# E73N30.net
KiCad netlist of a schematic drawn in Altium Designer
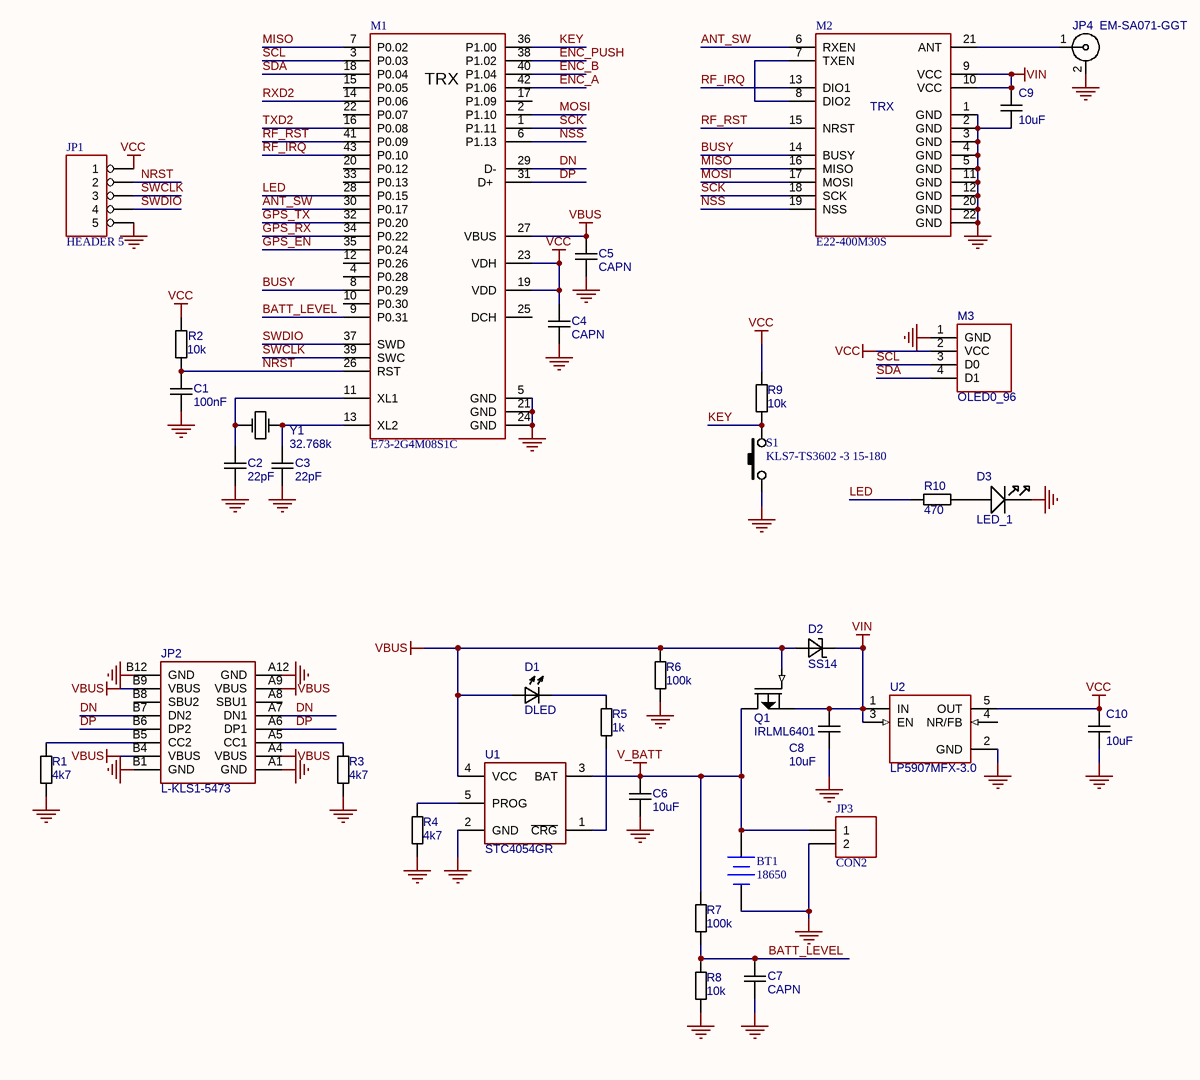
[diagram p0: E73N30.SchDoc]

(export (version "E")
  (design (tool "Eeschema 10.0.6"))
  (components
    (comp (ref "BT1")
      (value "18650")
      (footprint "18650")
      (description "Multicell Battery")
      (fields (field (name "PUBLISHER") "Altium Limited"))
      (libsource (lib "zucker") (part "Battery"))
    )
    (comp (ref "C1")
      (value "100nF")
      (footprint "C-0603")
      (fields (field (name "VOLTAGE") "50V"))
      (libsource (lib "Passive") (part "CAPN"))
    )
    (comp (ref "C2")
      (value "22pF")
      (footprint "C-0603")
      (fields (field (name "VOLTAGE") "50V"))
      (libsource (lib "Passive") (part "CAPN"))
    )
    (comp (ref "C3")
      (value "22pF")
      (footprint "C-0603")
      (fields (field (name "VOLTAGE") "50V"))
      (libsource (lib "Passive") (part "CAPN"))
    )
    (comp (ref "C4")
      (value "CAPN")
      (footprint "C-0603")
      (fields (field (name "VOLTAGE") "50V"))
      (libsource (lib "Passive") (part "CAPN"))
    )
    (comp (ref "C5")
      (value "CAPN")
      (footprint "C-0603")
      (fields (field (name "VOLTAGE") "50V"))
      (libsource (lib "Passive") (part "CAPN"))
    )
    (comp (ref "C6")
      (value "10uF")
      (footprint "C-0805")
      (fields (field (name "VOLTAGE") "50V"))
      (libsource (lib "Passive") (part "CAPN"))
    )
    (comp (ref "C7")
      (value "CAPN")
      (footprint "C-0603")
      (fields (field (name "VOLTAGE") "50V"))
      (libsource (lib "Passive") (part "CAPN"))
    )
    (comp (ref "C8")
      (value "10uF")
      (footprint "C-0805")
      (fields (field (name "VOLTAGE") "50V"))
      (libsource (lib "Passive") (part "CAPN"))
    )
    (comp (ref "C9")
      (value "10uF")
      (footprint "C-0805")
      (fields (field (name "VOLTAGE") "50V"))
      (libsource (lib "Passive") (part "CAPN"))
    )
    (comp (ref "C10")
      (value "10uF")
      (footprint "C-0805")
      (fields (field (name "VOLTAGE") "50V"))
      (libsource (lib "Passive") (part "CAPN"))
    )
    (comp (ref "D1") (value "DLED") (footprint "LED0805") (libsource (lib "Diodes") (part "DLED")))
    (comp (ref "D2") (value "SS14") (footprint "D-SMA") (libsource (lib "Diodes") (part "DIODSH")))
    (comp (ref "D3") (value "LED_1") (footprint "LED_0805") (libsource (lib "Diodes") (part "LED_1")))
    (comp (ref "JP1")
      (value "HEADER 5")
      (footprint "PLS1-5")
      (libsource (lib "Connectors") (part "HEADER 5"))
    )
    (comp (ref "JP2")
      (value "L-KLS1-5473")
      (footprint "USB_C_SMD_SLOT")
      (libsource (lib "Connectors") (part "L-KLS1-5473"))
    )
    (comp (ref "JP3") (value "CON2") (footprint "WH-02R") (libsource (lib "Connectors") (part "CON2")))
    (comp (ref "JP4")
      (value "EM-SA071-GGT")
      (footprint "SMA_F_EDGE")
      (description "SMA Female R/A PCB Mount")
      (libsource (lib "Connectors") (part "SMA"))
    )
    (comp (ref "M1")
      (value "E73-2G4M08S1C")
      (footprint "E73-2G4M08S1CX")
      (libsource (lib "RFmodules") (part "E73-2G4M08S1C"))
    )
    (comp (ref "M2")
      (value "E22-400M30S")
      (footprint "PE22(400M30S)")
      (libsource (lib "RFmodules") (part "E22"))
    )
    (comp (ref "M3")
      (value "OLED0_96")
      (footprint "OLED096_I2C")
      (libsource (lib "RFmodules") (part "OLED0_96_I2C"))
    )
    (comp (ref "Q1") (value "IRLML6401") (footprint "SOT-23") (libsource (lib "Discrete") (part "MOSF-P")))
    (comp (ref "R1") (value "4k7") (footprint "R-0603") (libsource (lib "") (part "RES_1")))
    (comp (ref "R2") (value "10k") (footprint "R-0603") (libsource (lib "Passive") (part "RES")))
    (comp (ref "R3") (value "4k7") (footprint "R-0603") (libsource (lib "") (part "RES_1")))
    (comp (ref "R4") (value "4k7") (footprint "R-0603") (libsource (lib "") (part "RES_1")))
    (comp (ref "R5") (value "1k") (footprint "R-0603") (libsource (lib "Passive") (part "RES")))
    (comp (ref "R6") (value "100k") (footprint "R-0603") (libsource (lib "Passive") (part "RES")))
    (comp (ref "R7") (value "100k") (footprint "R-0603") (libsource (lib "Passive") (part "RES")))
    (comp (ref "R8") (value "10k") (footprint "R-0603") (libsource (lib "Passive") (part "RES")))
    (comp (ref "R9") (value "10k") (footprint "R-0603") (libsource (lib "") (part "RES_3")))
    (comp (ref "R10") (value "470") (footprint "R-0603") (libsource (lib "") (part "RES_2")))
    (comp (ref "S1")
      (value "KLS7-TS3602 -3 15-180")
      (footprint "KN_MIN")
      (libsource (lib "Switches") (part "SW-1"))
    )
    (comp (ref "U1") (value "STC4054GR") (footprint "SOT-23-5") (libsource (lib "Power") (part "STC4054")))
    (comp (ref "U2")
      (value "LP5907MFX-3.0")
      (footprint "SOT-23-5")
      (description "250mA Low-Dropout Regulator")
      (libsource (lib "ICs") (part "LP5907"))
    )
    (comp (ref "Y1") (value "32.768k") (footprint "KX-327") (libsource (lib "Passive") (part "Y")))
  )
  (nets
    (net (code "1") (name "/ANT_SW") (class "Default")
      (node (ref "M1") (pin "30") (pinfunction "P0.17_30") (pintype "passive"))
      (node (ref "M2") (pin "6") (pinfunction "RXEN_6") (pintype "passive"))
    )
    (net (code "2") (name "/BATT_LEVEL") (class "Default")
      (node (ref "C7") (pin "1") (pinfunction "1_1") (pintype "passive"))
      (node (ref "M1") (pin "9") (pinfunction "P0.31_9") (pintype "passive"))
      (node (ref "R7") (pin "1") (pinfunction "1_1") (pintype "passive"))
      (node (ref "R8") (pin "2") (pinfunction "2_2") (pintype "passive"))
    )
    (net (code "3") (name "/BUSY") (class "Default")
      (node (ref "M1") (pin "8") (pinfunction "P0.29_8") (pintype "passive"))
      (node (ref "M2") (pin "14") (pinfunction "BUSY_14") (pintype "passive"))
    )
    (net (code "4") (name "/DN") (class "Default")
      (node (ref "JP2") (pin "A7") (pinfunction "DN1_A7") (pintype "passive"))
      (node (ref "JP2") (pin "B7") (pinfunction "DN2_B7") (pintype "passive"))
      (node (ref "M1") (pin "29") (pinfunction "D-_29") (pintype "passive"))
    )
    (net (code "5") (name "/DP") (class "Default")
      (node (ref "JP2") (pin "A6") (pinfunction "DP1_A6") (pintype "passive"))
      (node (ref "JP2") (pin "B6") (pinfunction "DP2_B6") (pintype "passive"))
      (node (ref "M1") (pin "31") (pinfunction "D+_31") (pintype "passive"))
    )
    (net (code "6") (name "/ENC_A") (class "Default")
      (node (ref "M1") (pin "42") (pinfunction "P1.06_42") (pintype "passive"))
    )
    (net (code "7") (name "/ENC_B") (class "Default")
      (node (ref "M1") (pin "40") (pinfunction "P1.04_40") (pintype "passive"))
    )
    (net (code "8") (name "/ENC_PUSH") (class "Default")
      (node (ref "M1") (pin "38") (pinfunction "P1.02_38") (pintype "passive"))
    )
    (net (code "9") (name "/GPS_EN") (class "Default")
      (node (ref "M1") (pin "35") (pinfunction "P0.24_35") (pintype "passive"))
    )
    (net (code "10") (name "/GPS_RX") (class "Default")
      (node (ref "M1") (pin "34") (pinfunction "P0.22_34") (pintype "passive"))
    )
    (net (code "11") (name "/GPS_TX") (class "Default")
      (node (ref "M1") (pin "32") (pinfunction "P0.20_32") (pintype "passive"))
    )
    (net (code "12") (name "/KEY") (class "Default")
      (node (ref "M1") (pin "36") (pinfunction "P1.00_36") (pintype "passive"))
      (node (ref "R9") (pin "2") (pinfunction "2_2") (pintype "passive"))
      (node (ref "S1") (pin "2") (pinfunction "2_2") (pintype "passive"))
    )
    (net (code "13") (name "/LED") (class "Default")
      (node (ref "M1") (pin "28") (pinfunction "P0.15_28") (pintype "passive"))
      (node (ref "R10") (pin "2") (pinfunction "2_2") (pintype "passive"))
    )
    (net (code "14") (name "/MISO") (class "Default")
      (node (ref "M1") (pin "7") (pinfunction "P0.02_7") (pintype "passive"))
      (node (ref "M2") (pin "16") (pinfunction "MISO_16") (pintype "passive"))
    )
    (net (code "15") (name "/MOSI") (class "Default")
      (node (ref "M1") (pin "2") (pinfunction "P1.10_2") (pintype "passive"))
      (node (ref "M2") (pin "17") (pinfunction "MOSI_17") (pintype "passive"))
    )
    (net (code "16") (name "/NRST") (class "Default")
      (node (ref "C1") (pin "2") (pinfunction "2_2") (pintype "passive"))
      (node (ref "JP1") (pin "2") (pinfunction "2_2") (pintype "passive"))
      (node (ref "M1") (pin "26") (pinfunction "RST_26") (pintype "passive"))
      (node (ref "R2") (pin "1") (pinfunction "1_1") (pintype "passive"))
    )
    (net (code "17") (name "/NSS") (class "Default")
      (node (ref "M1") (pin "6") (pinfunction "P1.13_6") (pintype "passive"))
      (node (ref "M2") (pin "19") (pinfunction "NSS_19") (pintype "passive"))
    )
    (net (code "18") (name "/RF_IRQ") (class "Default")
      (node (ref "M1") (pin "43") (pinfunction "P0.10_43") (pintype "passive"))
      (node (ref "M2") (pin "13") (pinfunction "DIO1_13") (pintype "passive"))
    )
    (net (code "19") (name "/RF_RST") (class "Default")
      (node (ref "M1") (pin "41") (pinfunction "P0.09_41") (pintype "passive"))
      (node (ref "M2") (pin "15") (pinfunction "NRST_15") (pintype "passive"))
    )
    (net (code "20") (name "/RXD2") (class "Default")
      (node (ref "M1") (pin "14") (pinfunction "P0.06_14") (pintype "passive"))
    )
    (net (code "21") (name "/SCK") (class "Default")
      (node (ref "M1") (pin "1") (pinfunction "_P1.11_1") (pintype "passive"))
      (node (ref "M2") (pin "18") (pinfunction "SCK_18") (pintype "passive"))
    )
    (net (code "22") (name "/SCL") (class "Default")
      (node (ref "M1") (pin "3") (pinfunction "P0.03_3") (pintype "passive"))
      (node (ref "M3") (pin "3") (pinfunction "D0_3") (pintype "passive"))
    )
    (net (code "23") (name "/SDA") (class "Default")
      (node (ref "M1") (pin "18") (pinfunction "P0.04_18") (pintype "passive"))
      (node (ref "M3") (pin "4") (pinfunction "D1_4") (pintype "passive"))
    )
    (net (code "24") (name "/SWCLK") (class "Default")
      (node (ref "JP1") (pin "3") (pinfunction "3_3") (pintype "passive"))
      (node (ref "M1") (pin "39") (pinfunction "SWC_39") (pintype "passive"))
    )
    (net (code "25") (name "/SWDIO") (class "Default")
      (node (ref "JP1") (pin "4") (pinfunction "4_4") (pintype "passive"))
      (node (ref "M1") (pin "37") (pinfunction "SWD_37") (pintype "passive"))
    )
    (net (code "26") (name "/TXD2") (class "Default")
      (node (ref "M1") (pin "16") (pinfunction "P0.08_16") (pintype "passive"))
    )
    (net (code "27") (name "GND") (class "Default")
      (node (ref "BT1") (pin "2") (pinfunction "-_2") (pintype "passive"))
      (node (ref "C1") (pin "1") (pinfunction "1_1") (pintype "passive"))
      (node (ref "C10") (pin "2") (pinfunction "2_2") (pintype "passive"))
      (node (ref "C2") (pin "1") (pinfunction "1_1") (pintype "passive"))
      (node (ref "C3") (pin "1") (pinfunction "1_1") (pintype "passive"))
      (node (ref "C4") (pin "2") (pinfunction "2_2") (pintype "passive"))
      (node (ref "C5") (pin "2") (pinfunction "2_2") (pintype "passive"))
      (node (ref "C6") (pin "2") (pinfunction "2_2") (pintype "passive"))
      (node (ref "C7") (pin "2") (pinfunction "2_2") (pintype "passive"))
      (node (ref "C8") (pin "2") (pinfunction "2_2") (pintype "passive"))
      (node (ref "C9") (pin "2") (pinfunction "2_2") (pintype "passive"))
      (node (ref "D3") (pin "K") (pinfunction "CATHODE_K") (pintype "passive"))
      (node (ref "JP1") (pin "5") (pinfunction "5_5") (pintype "passive"))
      (node (ref "JP2") (pin "A1") (pinfunction "GND_A1") (pintype "passive"))
      (node (ref "JP2") (pin "A12") (pinfunction "GND_A12") (pintype "passive"))
      (node (ref "JP2") (pin "B1") (pinfunction "GND_B1") (pintype "passive"))
      (node (ref "JP2") (pin "B12") (pinfunction "GND_B12") (pintype "passive"))
      (node (ref "JP3") (pin "2") (pinfunction "2_2") (pintype "passive"))
      (node (ref "JP4") (pin "2") (pinfunction "2_2") (pintype "passive"))
      (node (ref "M1") (pin "21") (pinfunction "GND_21") (pintype "passive"))
      (node (ref "M1") (pin "24") (pinfunction "GND_24") (pintype "passive"))
      (node (ref "M1") (pin "5") (pinfunction "GND_5") (pintype "passive"))
      (node (ref "M2") (pin "1") (pinfunction "GND_1") (pintype "passive"))
      (node (ref "M2") (pin "11") (pinfunction "GND_11") (pintype "passive"))
      (node (ref "M2") (pin "12") (pinfunction "GND_12") (pintype "passive"))
      (node (ref "M2") (pin "2") (pinfunction "GND_2") (pintype "passive"))
      (node (ref "M2") (pin "20") (pinfunction "GND_20") (pintype "passive"))
      (node (ref "M2") (pin "22") (pinfunction "GND_22") (pintype "passive"))
      (node (ref "M2") (pin "3") (pinfunction "GND_3") (pintype "passive"))
      (node (ref "M2") (pin "4") (pinfunction "GND_4") (pintype "passive"))
      (node (ref "M2") (pin "5") (pinfunction "GND_5") (pintype "passive"))
      (node (ref "M3") (pin "1") (pinfunction "GND_1") (pintype "passive"))
      (node (ref "R1") (pin "1") (pinfunction "1_1") (pintype "passive"))
      (node (ref "R3") (pin "1") (pinfunction "1_1") (pintype "passive"))
      (node (ref "R4") (pin "1") (pinfunction "1_1") (pintype "passive"))
      (node (ref "R6") (pin "1") (pinfunction "1_1") (pintype "passive"))
      (node (ref "R8") (pin "1") (pinfunction "1_1") (pintype "passive"))
      (node (ref "S1") (pin "1") (pinfunction "1_1") (pintype "passive"))
      (node (ref "U1") (pin "2") (pinfunction "GND_2") (pintype "passive"))
      (node (ref "U2") (pin "2") (pinfunction "GND_2") (pintype "power_in"))
    )
    (net (code "28") (name "Net-(D1-Pad2)") (class "Default")
      (node (ref "D1") (pin "2") (pinfunction "2_2") (pintype "passive"))
      (node (ref "R5") (pin "2") (pinfunction "2_2") (pintype "passive"))
    )
    (net (code "29") (name "Net-(D3-ANODE)") (class "Default")
      (node (ref "D3") (pin "A") (pinfunction "ANODE_A") (pintype "passive"))
      (node (ref "R10") (pin "1") (pinfunction "1_1") (pintype "passive"))
    )
    (net (code "30") (name "Net-(JP2-CC1)") (class "Default")
      (node (ref "JP2") (pin "A5") (pinfunction "CC1_A5") (pintype "passive"))
      (node (ref "R3") (pin "2") (pinfunction "2_2") (pintype "passive"))
    )
    (net (code "31") (name "Net-(JP2-CC2)") (class "Default")
      (node (ref "JP2") (pin "B5") (pinfunction "CC2_B5") (pintype "passive"))
      (node (ref "R1") (pin "2") (pinfunction "2_2") (pintype "passive"))
    )
    (net (code "32") (name "Net-(M1-XL1)") (class "Default")
      (node (ref "C2") (pin "2") (pinfunction "2_2") (pintype "passive"))
      (node (ref "M1") (pin "11") (pinfunction "XL1_11") (pintype "passive"))
      (node (ref "Y1") (pin "2") (pinfunction "2_2") (pintype "passive"))
    )
    (net (code "33") (name "Net-(M1-XL2)") (class "Default")
      (node (ref "C3") (pin "2") (pinfunction "2_2") (pintype "passive"))
      (node (ref "M1") (pin "13") (pinfunction "XL2_13") (pintype "passive"))
      (node (ref "Y1") (pin "1") (pinfunction "1_1") (pintype "passive"))
    )
    (net (code "34") (name "Net-(M2-ANT)") (class "Default")
      (node (ref "JP4") (pin "1") (pinfunction "1_1") (pintype "passive"))
      (node (ref "M2") (pin "21") (pinfunction "ANT_21") (pintype "passive"))
    )
    (net (code "35") (name "Net-(M2-DIO2)") (class "Default")
      (node (ref "M2") (pin "7") (pinfunction "TXEN_7") (pintype "passive"))
      (node (ref "M2") (pin "8") (pinfunction "DIO2_8") (pintype "passive"))
    )
    (net (code "36") (name "Net-(U1-PROG)") (class "Default")
      (node (ref "R4") (pin "2") (pinfunction "2_2") (pintype "passive"))
      (node (ref "U1") (pin "5") (pinfunction "PROG_5") (pintype "passive"))
    )
    (net (code "37") (name "Net-(U1-~{CRG})") (class "Default")
      (node (ref "R5") (pin "1") (pinfunction "1_1") (pintype "passive"))
      (node (ref "U1") (pin "1") (pinfunction "~{CRG}_1") (pintype "passive"))
    )
    (net (code "38") (name "VBUS") (class "Default")
      (node (ref "C5") (pin "1") (pinfunction "1_1") (pintype "passive"))
      (node (ref "D1") (pin "1") (pinfunction "1_1") (pintype "passive"))
      (node (ref "D2") (pin "1") (pinfunction "1_1") (pintype "passive"))
      (node (ref "JP2") (pin "A4") (pinfunction "VBUS_A4") (pintype "passive"))
      (node (ref "JP2") (pin "A9") (pinfunction "VBUS_A9") (pintype "passive"))
      (node (ref "JP2") (pin "B4") (pinfunction "VBUS_B4") (pintype "passive"))
      (node (ref "JP2") (pin "B9") (pinfunction "VBUS_B9") (pintype "passive"))
      (node (ref "M1") (pin "27") (pinfunction "VBUS_27") (pintype "passive"))
      (node (ref "Q1") (pin "1") (pinfunction "GATE_1") (pintype "input"))
      (node (ref "R6") (pin "2") (pinfunction "2_2") (pintype "passive"))
      (node (ref "U1") (pin "4") (pinfunction "VCC_4") (pintype "passive"))
    )
    (net (code "39") (name "VCC") (class "Default")
      (node (ref "C10") (pin "1") (pinfunction "1_1") (pintype "passive"))
      (node (ref "C4") (pin "1") (pinfunction "1_1") (pintype "passive"))
      (node (ref "JP1") (pin "1") (pinfunction "1_1") (pintype "passive"))
      (node (ref "M1") (pin "19") (pinfunction "VDD_19") (pintype "passive"))
      (node (ref "M1") (pin "23") (pinfunction "VDH_23") (pintype "passive"))
      (node (ref "M3") (pin "2") (pinfunction "VCC_2") (pintype "passive"))
      (node (ref "R2") (pin "2") (pinfunction "2_2") (pintype "passive"))
      (node (ref "R9") (pin "1") (pinfunction "1_1") (pintype "passive"))
      (node (ref "U2") (pin "5") (pinfunction "OUT_5") (pintype "power_in"))
    )
    (net (code "40") (name "VIN") (class "Default")
      (node (ref "C8") (pin "1") (pinfunction "1_1") (pintype "passive"))
      (node (ref "C9") (pin "1") (pinfunction "1_1") (pintype "passive"))
      (node (ref "D2") (pin "2") (pinfunction "2_2") (pintype "passive"))
      (node (ref "M2") (pin "10") (pinfunction "VCC_10") (pintype "passive"))
      (node (ref "M2") (pin "9") (pinfunction "VCC_9") (pintype "passive"))
      (node (ref "Q1") (pin "2") (pinfunction "SOURCE_2") (pintype "passive"))
      (node (ref "U2") (pin "1") (pinfunction "IN_1") (pintype "power_in"))
      (node (ref "U2") (pin "3") (pinfunction "EN_3") (pintype "input"))
    )
    (net (code "41") (name "VSS") (class "Default")
      (node (ref "JP2") (pin "17") (pinfunction "VSS_17") (pintype "power_in"))
    )
    (net (code "42") (name "V_BATT") (class "Default")
      (node (ref "BT1") (pin "1") (pinfunction "+_1") (pintype "passive"))
      (node (ref "C6") (pin "1") (pinfunction "1_1") (pintype "passive"))
      (node (ref "JP3") (pin "1") (pinfunction "1_1") (pintype "passive"))
      (node (ref "Q1") (pin "3") (pinfunction "DRAIN_3") (pintype "passive"))
      (node (ref "R7") (pin "2") (pinfunction "2_2") (pintype "passive"))
      (node (ref "U1") (pin "3") (pinfunction "BAT_3") (pintype "passive"))
    )
    (net (code "43") (name "unconnected-(JP2-SBU1-PadA8)") (class "Default")
      (node (ref "JP2") (pin "A8") (pinfunction "SBU1_A8") (pintype "passive"))
    )
    (net (code "44") (name "unconnected-(JP2-SBU2-PadB8)") (class "Default")
      (node (ref "JP2") (pin "B8") (pinfunction "SBU2_B8") (pintype "passive"))
    )
    (net (code "45") (name "unconnected-(M1-DCH-Pad25)") (class "Default")
      (node (ref "M1") (pin "25") (pinfunction "DCH_25") (pintype "passive"))
    )
    (net (code "46") (name "unconnected-(M1-P0.05-Pad15)") (class "Default")
      (node (ref "M1") (pin "15") (pinfunction "P0.05_15") (pintype "passive"))
    )
    (net (code "47") (name "unconnected-(M1-P0.07-Pad22)") (class "Default")
      (node (ref "M1") (pin "22") (pinfunction "P0.07_22") (pintype "passive"))
    )
    (net (code "48") (name "unconnected-(M1-P0.12-Pad20)") (class "Default")
      (node (ref "M1") (pin "20") (pinfunction "P0.12_20") (pintype "passive"))
    )
    (net (code "49") (name "unconnected-(M1-P0.13-Pad33)") (class "Default")
      (node (ref "M1") (pin "33") (pinfunction "P0.13_33") (pintype "passive"))
    )
    (net (code "50") (name "unconnected-(M1-P0.26-Pad12)") (class "Default")
      (node (ref "M1") (pin "12") (pinfunction "P0.26_12") (pintype "passive"))
    )
    (net (code "51") (name "unconnected-(M1-P0.28-Pad4)") (class "Default")
      (node (ref "M1") (pin "4") (pinfunction "P0.28_4") (pintype "passive"))
    )
    (net (code "52") (name "unconnected-(M1-P0.30-Pad10)") (class "Default")
      (node (ref "M1") (pin "10") (pinfunction "P0.30_10") (pintype "passive"))
    )
    (net (code "53") (name "unconnected-(M1-P1.09-Pad17)") (class "Default")
      (node (ref "M1") (pin "17") (pinfunction "P1.09_17") (pintype "passive"))
    )
    (net (code "54") (name "unconnected-(U2-NR{slash}FB-Pad4)") (class "Default")
      (node (ref "U2") (pin "4") (pinfunction "NR/FB_4") (pintype "input"))
    )
  )
)
